# SCH.net
KiCad netlist of a schematic drawn in EasyEDA Pro
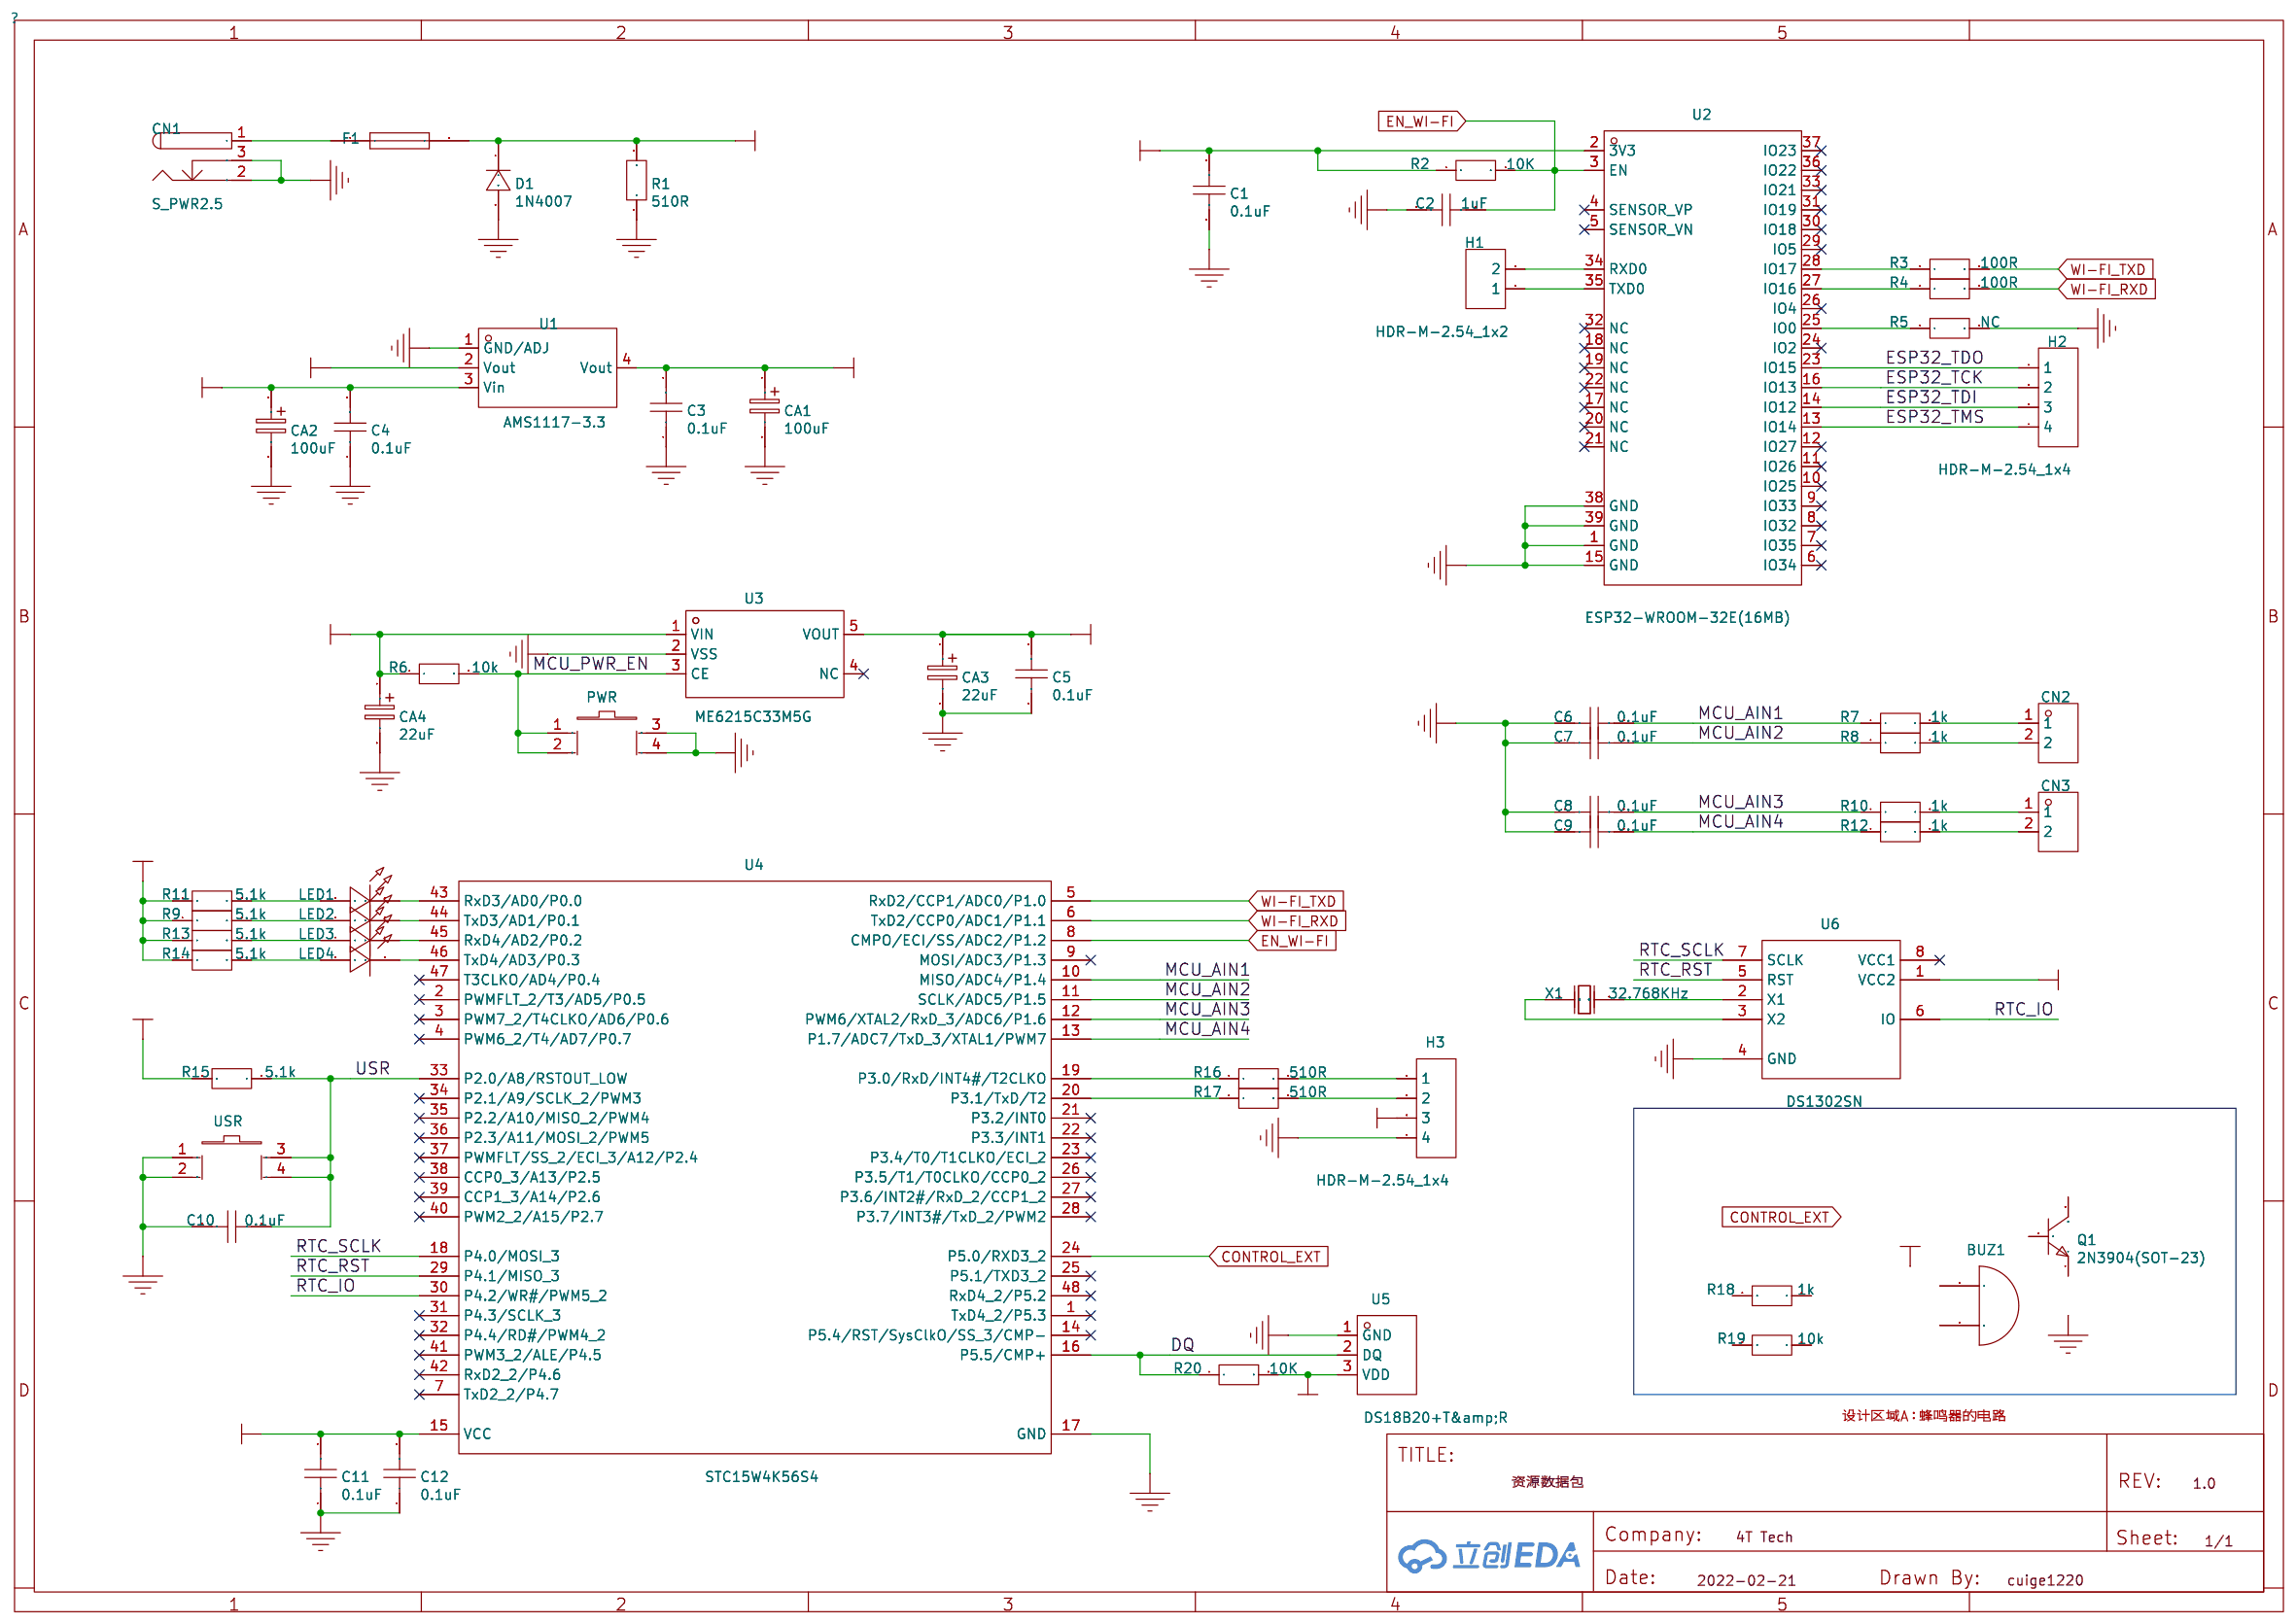
[diagram p0: schematic sheet]

(export (version "E")
  (design (tool "Eeschema 10.0.6"))
  (components
    (comp (ref "BUZ1") (value "BUZ1") (libsource (lib "easyedapro") (part "BUZ1")))
    (comp (ref "C1") (value "0.1uF") (libsource (lib "easyedapro") (part "0.1uF")))
    (comp (ref "C2") (value "1uF") (libsource (lib "easyedapro") (part "1uF")))
    (comp (ref "C3") (value "0.1uF") (libsource (lib "easyedapro") (part "0.1uF")))
    (comp (ref "C4") (value "0.1uF") (libsource (lib "easyedapro") (part "0.1uF")))
    (comp (ref "C5") (value "0.1uF") (libsource (lib "easyedapro") (part "0.1uF")))
    (comp (ref "C6") (value "0.1uF") (libsource (lib "easyedapro") (part "0.1uF")))
    (comp (ref "C7") (value "0.1uF") (libsource (lib "easyedapro") (part "0.1uF")))
    (comp (ref "C8") (value "0.1uF") (libsource (lib "easyedapro") (part "0.1uF")))
    (comp (ref "C9") (value "0.1uF") (libsource (lib "easyedapro") (part "0.1uF")))
    (comp (ref "C10") (value "0.1uF") (libsource (lib "easyedapro") (part "0.1uF")))
    (comp (ref "C11") (value "0.1uF") (libsource (lib "easyedapro") (part "0.1uF")))
    (comp (ref "C12") (value "0.1uF") (libsource (lib "easyedapro") (part "0.1uF")))
    (comp (ref "CA1") (value "100uF") (libsource (lib "easyedapro") (part "100uF")))
    (comp (ref "CA2") (value "100uF") (libsource (lib "easyedapro") (part "100uF")))
    (comp (ref "CA3") (value "22uF") (libsource (lib "easyedapro") (part "22uF")))
    (comp (ref "CA4") (value "22uF") (libsource (lib "easyedapro") (part "22uF")))
    (comp (ref "CN1") (value "S_PWR2.5") (libsource (lib "easyedapro") (part "S_PWR2.5")))
    (comp (ref "CN2")
      (value "DB128L-5.08-2P")
      (fields (field (name "Manufacturer") "DIBO"))
      (libsource (lib "easyedapro") (part "DB128L-5.08-2P"))
    )
    (comp (ref "CN3")
      (value "DB128L-5.08-2P")
      (fields (field (name "Manufacturer") "DIBO"))
      (libsource (lib "easyedapro") (part "DB128L-5.08-2P"))
    )
    (comp (ref "D1")
      (value "1N4007")
      (fields (field (name "Manufacturer") "SEMTECH"))
      (libsource (lib "easyedapro") (part "1N4007"))
    )
    (comp (ref "F1")
      (value "ASMD1210-075")
      (fields (field (name "Publisher") "Altium Limited"))
      (libsource (lib "easyedapro") (part "ASMD1210-075"))
    )
    (comp (ref "H1") (value "HDR-M-2.54_1x2") (libsource (lib "easyedapro") (part "HDR-M-2.54_1x2")))
    (comp (ref "H2") (value "HDR-M-2.54_1x4") (libsource (lib "easyedapro") (part "HDR-M-2.54_1x4")))
    (comp (ref "H3") (value "HDR-M-2.54_1x4") (libsource (lib "easyedapro") (part "HDR-M-2.54_1x4")))
    (comp (ref "LED1")
      (value "LED-TH-3mm_R")
      (fields
        (field (name "Manufacturer Part") "204-10SDRD/S530-A3-L")
        (field (name "Manufacturer") "EVERLIGHT(台湾亿光)")
      )
      (libsource (lib "easyedapro") (part "LED-TH-3mm_R"))
    )
    (comp (ref "LED2")
      (value "LED-TH-3mm_R")
      (fields
        (field (name "Manufacturer Part") "204-10SDRD/S530-A3-L")
        (field (name "Manufacturer") "EVERLIGHT(台湾亿光)")
      )
      (libsource (lib "easyedapro") (part "LED-TH-3mm_R"))
    )
    (comp (ref "LED3")
      (value "LED-TH-3mm_R")
      (fields
        (field (name "Manufacturer Part") "204-10SDRD/S530-A3-L")
        (field (name "Manufacturer") "EVERLIGHT(台湾亿光)")
      )
      (libsource (lib "easyedapro") (part "LED-TH-3mm_R"))
    )
    (comp (ref "LED4")
      (value "LED-TH-3mm_R")
      (fields
        (field (name "Manufacturer Part") "204-10SDRD/S530-A3-L")
        (field (name "Manufacturer") "EVERLIGHT(台湾亿光)")
      )
      (libsource (lib "easyedapro") (part "LED-TH-3mm_R"))
    )
    (comp (ref "PWR")
      (value "6x6x6Plastic head")
      (fields (field (name "Manufacturer") "ReliaPro"))
      (libsource (lib "easyedapro") (part "6x6x6Plastic head"))
    )
    (comp (ref "Q1")
      (value "2N3904(SOT-23)")
      (fields (field (name "Manufacturer Part") "2n3904S-RTK/PS") (field (name "Manufacturer") "KEC"))
      (libsource (lib "easyedapro") (part "2N3904(SOT-23)"))
    )
    (comp (ref "R1") (value "510R") (libsource (lib "easyedapro") (part "510R")))
    (comp (ref "R2") (value "10K") (libsource (lib "easyedapro") (part "10k")))
    (comp (ref "R3") (value "100R") (libsource (lib "easyedapro") (part "100R")))
    (comp (ref "R4") (value "100R") (libsource (lib "easyedapro") (part "100R")))
    (comp (ref "R5") (value "NC") (libsource (lib "easyedapro") (part "NC")))
    (comp (ref "R6") (value "10k") (libsource (lib "easyedapro") (part "10k")))
    (comp (ref "R7") (value "1k") (libsource (lib "easyedapro") (part "1K")))
    (comp (ref "R8") (value "1k") (libsource (lib "easyedapro") (part "1K")))
    (comp (ref "R9") (value "5.1k") (libsource (lib "easyedapro") (part "5.1k")))
    (comp (ref "R10") (value "1k") (libsource (lib "easyedapro") (part "1K")))
    (comp (ref "R11") (value "5.1k") (libsource (lib "easyedapro") (part "5.1k")))
    (comp (ref "R12") (value "1k") (libsource (lib "easyedapro") (part "1K")))
    (comp (ref "R13") (value "5.1k") (libsource (lib "easyedapro") (part "5.1k")))
    (comp (ref "R14") (value "5.1k") (libsource (lib "easyedapro") (part "5.1k")))
    (comp (ref "R15") (value "5.1k") (libsource (lib "easyedapro") (part "5.1k")))
    (comp (ref "R16") (value "510R") (libsource (lib "easyedapro") (part "510R")))
    (comp (ref "R17") (value "510R") (libsource (lib "easyedapro") (part "510R")))
    (comp (ref "R18") (value "1k") (libsource (lib "easyedapro") (part "1K")))
    (comp (ref "R19") (value "10k") (libsource (lib "easyedapro") (part "10k")))
    (comp (ref "R20") (value "10K") (libsource (lib "easyedapro") (part "10k")))
    (comp (ref "U1")
      (value "AMS1117-3.3")
      (fields (field (name "Manufacturer") "AMS"))
      (libsource (lib "easyedapro") (part "AMS1117-3.3"))
    )
    (comp (ref "U2")
      (value "ESP32-WROOM-32E(16MB)")
      (fields (field (name "Manufacturer") "Espressif Systems"))
      (libsource (lib "easyedapro") (part "ESP32-WROOM-32E(16MB)"))
    )
    (comp (ref "U3")
      (value "ME6215C33M5G")
      (fields (field (name "Manufacturer") "MICRONE"))
      (libsource (lib "easyedapro") (part "ME6215C33M5G"))
    )
    (comp (ref "U4")
      (value "STC15W4K56S4")
      (fields (field (name "Manufacturer") "STC"))
      (libsource (lib "easyedapro") (part "STC15W4K56S4"))
    )
    (comp (ref "U5")
      (value "DS18B20+T&amp;R")
      (fields (field (name "Manufacturer Part") "DS18B20+T&R") (field (name "Manufacturer") "MAXIM(美信)"))
      (libsource (lib "easyedapro") (part "DS18B20+T&amp;R"))
    )
    (comp (ref "U6") (value "DS1302SN") (libsource (lib "easyedapro") (part "DS1302SN")))
    (comp (ref "USR")
      (value "6x6x6Plastic head")
      (fields (field (name "Manufacturer") "ReliaPro"))
      (libsource (lib "easyedapro") (part "6x6x6Plastic head"))
    )
    (comp (ref "X1")
      (value "32.768KHz")
      (fields (field (name "Manufacturer Part") "CFS-20632768EZFB") (field (name "Manufacturer") "CITIZEN"))
      (libsource (lib "easyedapro") (part "32.768KHz"))
    )
  )
  (nets
    (net (code "1") (name "+5V0") (class "Default")
      (node (ref "C4") (pin "2") (pinfunction "2_2") (pintype "input"))
      (node (ref "CA2") (pin "1") (pinfunction "1_1") (pintype "input"))
      (node (ref "CA4") (pin "1") (pinfunction "1_1") (pintype "input"))
      (node (ref "D1") (pin "1") (pinfunction "1_1") (pintype "input"))
      (node (ref "F1") (pin "2") (pinfunction "2_2") (pintype "input"))
      (node (ref "R1") (pin "2") (pinfunction "2_2") (pintype "input"))
      (node (ref "R6") (pin "1") (pinfunction "1_1") (pintype "input"))
      (node (ref "U1") (pin "3") (pinfunction "Vin_3") (pintype "input"))
      (node (ref "U3") (pin "1") (pinfunction "VIN_1") (pintype "input"))
    )
    (net (code "2") (name "/DQ") (class "Default")
      (node (ref "R20") (pin "1") (pinfunction "1_1") (pintype "input"))
      (node (ref "U4") (pin "16") (pinfunction "P5.5/CMP+_16") (pintype "input"))
      (node (ref "U5") (pin "2") (pinfunction "DQ_2") (pintype "input"))
    )
    (net (code "3") (name "/ESP32_TCK") (class "Default")
      (node (ref "H2") (pin "2") (pinfunction "2_2") (pintype "input"))
      (node (ref "U2") (pin "16") (pinfunction "IO13_16") (pintype "input"))
    )
    (net (code "4") (name "/ESP32_TDI") (class "Default")
      (node (ref "H2") (pin "3") (pinfunction "3_3") (pintype "input"))
      (node (ref "U2") (pin "14") (pinfunction "IO12_14") (pintype "input"))
    )
    (net (code "5") (name "/ESP32_TDO") (class "Default")
      (node (ref "H2") (pin "1") (pinfunction "1_1") (pintype "input"))
      (node (ref "U2") (pin "23") (pinfunction "IO15_23") (pintype "input"))
    )
    (net (code "6") (name "/ESP32_TMS") (class "Default")
      (node (ref "H2") (pin "4") (pinfunction "4_4") (pintype "input"))
      (node (ref "U2") (pin "13") (pinfunction "IO14_13") (pintype "input"))
    )
    (net (code "7") (name "/MCU_AIN1") (class "Default")
      (node (ref "C6") (pin "2") (pinfunction "2_2") (pintype "input"))
      (node (ref "R7") (pin "1") (pinfunction "1_1") (pintype "input"))
      (node (ref "U4") (pin "10") (pinfunction "MISO/ADC4/P1.4_10") (pintype "input"))
    )
    (net (code "8") (name "/MCU_AIN2") (class "Default")
      (node (ref "C7") (pin "2") (pinfunction "2_2") (pintype "input"))
      (node (ref "R8") (pin "1") (pinfunction "1_1") (pintype "input"))
      (node (ref "U4") (pin "11") (pinfunction "SCLK/ADC5/P1.5_11") (pintype "input"))
    )
    (net (code "9") (name "/MCU_AIN3") (class "Default")
      (node (ref "C8") (pin "2") (pinfunction "2_2") (pintype "input"))
      (node (ref "R10") (pin "1") (pinfunction "1_1") (pintype "input"))
      (node (ref "U4") (pin "12") (pinfunction "PWM6/XTAL2/RxD_3/ADC6/P1.6_12") (pintype "input"))
    )
    (net (code "10") (name "/MCU_AIN4") (class "Default")
      (node (ref "C9") (pin "2") (pinfunction "2_2") (pintype "input"))
      (node (ref "R12") (pin "1") (pinfunction "1_1") (pintype "input"))
      (node (ref "U4") (pin "13") (pinfunction "P1.7/ADC7/TxD_3/XTAL1/PWM7_13") (pintype "input"))
    )
    (net (code "11") (name "/MCU_PWR_EN") (class "Default")
      (node (ref "PWR") (pin "1") (pinfunction "1_1") (pintype "input"))
      (node (ref "PWR") (pin "2") (pinfunction "2_2") (pintype "input"))
      (node (ref "R6") (pin "2") (pinfunction "2_2") (pintype "input"))
      (node (ref "U3") (pin "3") (pinfunction "CE_3") (pintype "input"))
    )
    (net (code "12") (name "/RTC_IO") (class "Default")
      (node (ref "U4") (pin "30") (pinfunction "P4.2/WR#/PWM5_2_30") (pintype "input"))
      (node (ref "U6") (pin "6") (pinfunction "IO_6") (pintype "bidirectional"))
    )
    (net (code "13") (name "/RTC_RST") (class "Default")
      (node (ref "U4") (pin "29") (pinfunction "P4.1/MISO_3_29") (pintype "input"))
      (node (ref "U6") (pin "5") (pinfunction "RST_5") (pintype "input"))
    )
    (net (code "14") (name "/RTC_SCLK") (class "Default")
      (node (ref "U4") (pin "18") (pinfunction "P4.0/MOSI_3_18") (pintype "input"))
      (node (ref "U6") (pin "7") (pinfunction "SCLK_7") (pintype "input"))
    )
    (net (code "15") (name "/USR") (class "Default")
      (node (ref "C10") (pin "1") (pinfunction "1_1") (pintype "input"))
      (node (ref "R15") (pin "1") (pinfunction "1_1") (pintype "input"))
      (node (ref "U4") (pin "33") (pinfunction "P2.0/A8/RSTOUT_LOW_33") (pintype "input"))
      (node (ref "USR") (pin "3") (pinfunction "3_3") (pintype "input"))
      (node (ref "USR") (pin "4") (pinfunction "4_4") (pintype "input"))
    )
    (net (code "16") (name "3.3V_MCU") (class "Default")
      (node (ref "C11") (pin "2") (pinfunction "2_2") (pintype "input"))
      (node (ref "C12") (pin "2") (pinfunction "2_2") (pintype "input"))
      (node (ref "C5") (pin "2") (pinfunction "2_2") (pintype "input"))
      (node (ref "CA3") (pin "1") (pinfunction "1_1") (pintype "input"))
      (node (ref "H3") (pin "3") (pinfunction "3_3") (pintype "input"))
      (node (ref "R11") (pin "1") (pinfunction "1_1") (pintype "input"))
      (node (ref "R13") (pin "1") (pinfunction "1_1") (pintype "input"))
      (node (ref "R14") (pin "1") (pinfunction "1_1") (pintype "input"))
      (node (ref "R15") (pin "2") (pinfunction "2_2") (pintype "input"))
      (node (ref "R20") (pin "2") (pinfunction "2_2") (pintype "input"))
      (node (ref "R9") (pin "1") (pinfunction "1_1") (pintype "input"))
      (node (ref "U3") (pin "5") (pinfunction "VOUT_5") (pintype "input"))
      (node (ref "U4") (pin "15") (pinfunction "VCC_15") (pintype "input"))
      (node (ref "U5") (pin "3") (pinfunction "VDD_3") (pintype "input"))
      (node (ref "U6") (pin "1") (pinfunction "VCC2_1") (pintype "input"))
    )
    (net (code "17") (name "3.3V_WIFI") (class "Default")
      (node (ref "C1") (pin "2") (pinfunction "2_2") (pintype "input"))
      (node (ref "C3") (pin "2") (pinfunction "2_2") (pintype "input"))
      (node (ref "CA1") (pin "1") (pinfunction "1_1") (pintype "input"))
      (node (ref "R2") (pin "1") (pinfunction "1_1") (pintype "input"))
      (node (ref "U1") (pin "2") (pinfunction "Vout_2") (pintype "input"))
      (node (ref "U1") (pin "4") (pinfunction "Vout_4") (pintype "input"))
      (node (ref "U2") (pin "2") (pinfunction "3V3_2") (pintype "input"))
    )
    (net (code "18") (name "CONTROL_EXT") (class "Default")
      (node (ref "U4") (pin "24") (pinfunction "P5.0/RXD3_2_24") (pintype "input"))
    )
    (net (code "19") (name "EN_WI-FI") (class "Default")
      (node (ref "C2") (pin "1") (pinfunction "1_1") (pintype "input"))
      (node (ref "R2") (pin "2") (pinfunction "2_2") (pintype "input"))
      (node (ref "U2") (pin "3") (pinfunction "EN_3") (pintype "input"))
      (node (ref "U4") (pin "8") (pinfunction "CMPO/ECI/SS/ADC2/P1.2_8") (pintype "input"))
    )
    (net (code "20") (name "GND") (class "Default")
      (node (ref "C1") (pin "1") (pinfunction "1_1") (pintype "input"))
      (node (ref "C10") (pin "2") (pinfunction "2_2") (pintype "input"))
      (node (ref "C11") (pin "1") (pinfunction "1_1") (pintype "input"))
      (node (ref "C12") (pin "1") (pinfunction "1_1") (pintype "input"))
      (node (ref "C2") (pin "2") (pinfunction "2_2") (pintype "input"))
      (node (ref "C3") (pin "1") (pinfunction "1_1") (pintype "input"))
      (node (ref "C4") (pin "1") (pinfunction "1_1") (pintype "input"))
      (node (ref "C5") (pin "1") (pinfunction "1_1") (pintype "input"))
      (node (ref "C6") (pin "1") (pinfunction "1_1") (pintype "input"))
      (node (ref "C7") (pin "1") (pinfunction "1_1") (pintype "input"))
      (node (ref "C8") (pin "1") (pinfunction "1_1") (pintype "input"))
      (node (ref "C9") (pin "1") (pinfunction "1_1") (pintype "input"))
      (node (ref "CA1") (pin "2") (pinfunction "2_2") (pintype "input"))
      (node (ref "CA2") (pin "2") (pinfunction "2_2") (pintype "input"))
      (node (ref "CA3") (pin "2") (pinfunction "2_2") (pintype "input"))
      (node (ref "CA4") (pin "2") (pinfunction "2_2") (pintype "input"))
      (node (ref "CN1") (pin "2") (pinfunction "2_2") (pintype "input"))
      (node (ref "CN1") (pin "3") (pinfunction "3_3") (pintype "input"))
      (node (ref "D1") (pin "2") (pinfunction "2_2") (pintype "input"))
      (node (ref "H3") (pin "4") (pinfunction "4_4") (pintype "input"))
      (node (ref "PWR") (pin "3") (pinfunction "3_3") (pintype "input"))
      (node (ref "PWR") (pin "4") (pinfunction "4_4") (pintype "input"))
      (node (ref "R1") (pin "1") (pinfunction "1_1") (pintype "input"))
      (node (ref "R5") (pin "2") (pinfunction "2_2") (pintype "input"))
      (node (ref "U1") (pin "1") (pinfunction "GND/ADJ_1") (pintype "input"))
      (node (ref "U2") (pin "1") (pinfunction "GND_1") (pintype "input"))
      (node (ref "U2") (pin "15") (pinfunction "GND_15") (pintype "input"))
      (node (ref "U2") (pin "38") (pinfunction "GND_38") (pintype "input"))
      (node (ref "U2") (pin "39") (pinfunction "GND_39") (pintype "input"))
      (node (ref "U3") (pin "2") (pinfunction "VSS_2") (pintype "input"))
      (node (ref "U4") (pin "17") (pinfunction "GND_17") (pintype "input"))
      (node (ref "U5") (pin "1") (pinfunction "GND_1") (pintype "input"))
      (node (ref "U6") (pin "4") (pinfunction "GND_4") (pintype "input"))
      (node (ref "USR") (pin "1") (pinfunction "1_1") (pintype "input"))
      (node (ref "USR") (pin "2") (pinfunction "2_2") (pintype "input"))
    )
    (net (code "21") (name "Net-(CN1-Pad1)") (class "Default")
      (node (ref "CN1") (pin "1") (pinfunction "1_1") (pintype "input"))
      (node (ref "F1") (pin "1") (pinfunction "1_1") (pintype "input"))
    )
    (net (code "22") (name "Net-(CN2-Pad1)") (class "Default")
      (node (ref "CN2") (pin "1") (pinfunction "1_1") (pintype "input"))
      (node (ref "R7") (pin "2") (pinfunction "2_2") (pintype "input"))
    )
    (net (code "23") (name "Net-(CN2-Pad2)") (class "Default")
      (node (ref "CN2") (pin "2") (pinfunction "2_2") (pintype "input"))
      (node (ref "R8") (pin "2") (pinfunction "2_2") (pintype "input"))
    )
    (net (code "24") (name "Net-(CN3-Pad1)") (class "Default")
      (node (ref "CN3") (pin "1") (pinfunction "1_1") (pintype "input"))
      (node (ref "R10") (pin "2") (pinfunction "2_2") (pintype "input"))
    )
    (net (code "25") (name "Net-(CN3-Pad2)") (class "Default")
      (node (ref "CN3") (pin "2") (pinfunction "2_2") (pintype "input"))
      (node (ref "R12") (pin "2") (pinfunction "2_2") (pintype "input"))
    )
    (net (code "26") (name "Net-(H3-Pad1)") (class "Default")
      (node (ref "H3") (pin "1") (pinfunction "1_1") (pintype "input"))
      (node (ref "R16") (pin "2") (pinfunction "2_2") (pintype "input"))
    )
    (net (code "27") (name "Net-(H3-Pad2)") (class "Default")
      (node (ref "H3") (pin "2") (pinfunction "2_2") (pintype "input"))
      (node (ref "R17") (pin "2") (pinfunction "2_2") (pintype "input"))
    )
    (net (code "28") (name "Net-(LED1-Pad1)") (class "Default")
      (node (ref "LED1") (pin "1") (pinfunction "1_1") (pintype "input"))
      (node (ref "R9") (pin "2") (pinfunction "2_2") (pintype "input"))
    )
    (net (code "29") (name "Net-(LED2-Pad1)") (class "Default")
      (node (ref "LED2") (pin "1") (pinfunction "1_1") (pintype "input"))
      (node (ref "R11") (pin "2") (pinfunction "2_2") (pintype "input"))
    )
    (net (code "30") (name "Net-(LED3-Pad1)") (class "Default")
      (node (ref "LED3") (pin "1") (pinfunction "1_1") (pintype "input"))
      (node (ref "R13") (pin "2") (pinfunction "2_2") (pintype "input"))
    )
    (net (code "31") (name "Net-(LED4-Pad1)") (class "Default")
      (node (ref "LED4") (pin "1") (pinfunction "1_1") (pintype "input"))
      (node (ref "R14") (pin "2") (pinfunction "2_2") (pintype "input"))
    )
    (net (code "32") (name "Net-(U2-IO0)") (class "Default")
      (node (ref "R5") (pin "1") (pinfunction "1_1") (pintype "input"))
      (node (ref "U2") (pin "25") (pinfunction "IO0_25") (pintype "input"))
    )
    (net (code "33") (name "Net-(U2-IO16)") (class "Default")
      (node (ref "R4") (pin "1") (pinfunction "1_1") (pintype "input"))
      (node (ref "U2") (pin "27") (pinfunction "IO16_27") (pintype "input"))
    )
    (net (code "34") (name "Net-(U2-IO17)") (class "Default")
      (node (ref "R3") (pin "1") (pinfunction "1_1") (pintype "input"))
      (node (ref "U2") (pin "28") (pinfunction "IO17_28") (pintype "input"))
    )
    (net (code "35") (name "Net-(U2-RXD0)") (class "Default")
      (node (ref "H1") (pin "2") (pinfunction "2_2") (pintype "input"))
      (node (ref "U2") (pin "34") (pinfunction "RXD0_34") (pintype "input"))
    )
    (net (code "36") (name "Net-(U2-TXD0)") (class "Default")
      (node (ref "H1") (pin "1") (pinfunction "1_1") (pintype "input"))
      (node (ref "U2") (pin "35") (pinfunction "TXD0_35") (pintype "input"))
    )
    (net (code "37") (name "Net-(U4-P3.0{slash}RxD{slash}INT4#{slash}T2CLKO)") (class "Default")
      (node (ref "R16") (pin "1") (pinfunction "1_1") (pintype "input"))
      (node (ref "U4") (pin "19") (pinfunction "P3.0/RxD/INT4#/T2CLKO_19") (pintype "input"))
    )
    (net (code "38") (name "Net-(U4-P3.1{slash}TxD{slash}T2)") (class "Default")
      (node (ref "R17") (pin "1") (pinfunction "1_1") (pintype "input"))
      (node (ref "U4") (pin "20") (pinfunction "P3.1/TxD/T2_20") (pintype "input"))
    )
    (net (code "39") (name "Net-(U4-RxD3{slash}AD0{slash}P0.0)") (class "Default")
      (node (ref "LED1") (pin "2") (pinfunction "2_2") (pintype "input"))
      (node (ref "U4") (pin "43") (pinfunction "RxD3/AD0/P0.0_43") (pintype "input"))
    )
    (net (code "40") (name "Net-(U4-RxD4{slash}AD2{slash}P0.2)") (class "Default")
      (node (ref "LED3") (pin "2") (pinfunction "2_2") (pintype "input"))
      (node (ref "U4") (pin "45") (pinfunction "RxD4/AD2/P0.2_45") (pintype "input"))
    )
    (net (code "41") (name "Net-(U4-TxD3{slash}AD1{slash}P0.1)") (class "Default")
      (node (ref "LED2") (pin "2") (pinfunction "2_2") (pintype "input"))
      (node (ref "U4") (pin "44") (pinfunction "TxD3/AD1/P0.1_44") (pintype "input"))
    )
    (net (code "42") (name "Net-(U4-TxD4{slash}AD3{slash}P0.3)") (class "Default")
      (node (ref "LED4") (pin "2") (pinfunction "2_2") (pintype "input"))
      (node (ref "U4") (pin "46") (pinfunction "TxD4/AD3/P0.3_46") (pintype "input"))
    )
    (net (code "43") (name "Net-(U6-X1)") (class "Default")
      (node (ref "U6") (pin "2") (pinfunction "X1_2") (pintype "input"))
      (node (ref "X1") (pin "2") (pinfunction "OSC2_2") (pintype "input"))
    )
    (net (code "44") (name "Net-(U6-X2)") (class "Default")
      (node (ref "U6") (pin "3") (pinfunction "X2_3") (pintype "input"))
      (node (ref "X1") (pin "1") (pinfunction "OSC1_1") (pintype "input"))
    )
    (net (code "45") (name "WI-FI_RXD") (class "Default")
      (node (ref "R4") (pin "2") (pinfunction "2_2") (pintype "input"))
      (node (ref "U4") (pin "6") (pinfunction "TxD2/CCP0/ADC1/P1.1_6") (pintype "input"))
    )
    (net (code "46") (name "WI-FI_TXD") (class "Default")
      (node (ref "R3") (pin "2") (pinfunction "2_2") (pintype "input"))
      (node (ref "U4") (pin "5") (pinfunction "RxD2/CCP1/ADC0/P1.0_5") (pintype "input"))
    )
    (net (code "47") (name "unconnected-(BUZ1-A-Pad1)") (class "Default")
      (node (ref "BUZ1") (pin "1") (pinfunction "A_1") (pintype "input"))
    )
    (net (code "48") (name "unconnected-(BUZ1-B-Pad2)") (class "Default")
      (node (ref "BUZ1") (pin "2") (pinfunction "B_2") (pintype "input"))
    )
    (net (code "49") (name "unconnected-(Q1-B-Pad2)") (class "Default")
      (node (ref "Q1") (pin "2") (pinfunction "B_2") (pintype "input"))
    )
    (net (code "50") (name "unconnected-(Q1-C-Pad3)") (class "Default")
      (node (ref "Q1") (pin "3") (pinfunction "C_3") (pintype "input"))
    )
    (net (code "51") (name "unconnected-(Q1-E-Pad1)") (class "Default")
      (node (ref "Q1") (pin "1") (pinfunction "E_1") (pintype "input"))
    )
    (net (code "52") (name "unconnected-(R18-Pad1)") (class "Default")
      (node (ref "R18") (pin "1") (pinfunction "1_1") (pintype "input"))
    )
    (net (code "53") (name "unconnected-(R18-Pad2)") (class "Default")
      (node (ref "R18") (pin "2") (pinfunction "2_2") (pintype "input"))
    )
    (net (code "54") (name "unconnected-(R19-Pad1)") (class "Default")
      (node (ref "R19") (pin "1") (pinfunction "1_1") (pintype "input"))
    )
    (net (code "55") (name "unconnected-(R19-Pad2)") (class "Default")
      (node (ref "R19") (pin "2") (pinfunction "2_2") (pintype "input"))
    )
    (net (code "56") (name "unconnected-(U2-IO2-Pad24)") (class "Default")
      (node (ref "U2") (pin "24") (pinfunction "IO2_24") (pintype "input+no_connect"))
    )
    (net (code "57") (name "unconnected-(U2-IO4-Pad26)") (class "Default")
      (node (ref "U2") (pin "26") (pinfunction "IO4_26") (pintype "input+no_connect"))
    )
    (net (code "58") (name "unconnected-(U2-IO5-Pad29)") (class "Default")
      (node (ref "U2") (pin "29") (pinfunction "IO5_29") (pintype "input+no_connect"))
    )
    (net (code "59") (name "unconnected-(U2-IO18-Pad30)") (class "Default")
      (node (ref "U2") (pin "30") (pinfunction "IO18_30") (pintype "input+no_connect"))
    )
    (net (code "60") (name "unconnected-(U2-IO19-Pad31)") (class "Default")
      (node (ref "U2") (pin "31") (pinfunction "IO19_31") (pintype "input+no_connect"))
    )
    (net (code "61") (name "unconnected-(U2-IO21-Pad33)") (class "Default")
      (node (ref "U2") (pin "33") (pinfunction "IO21_33") (pintype "input+no_connect"))
    )
    (net (code "62") (name "unconnected-(U2-IO22-Pad36)") (class "Default")
      (node (ref "U2") (pin "36") (pinfunction "IO22_36") (pintype "input+no_connect"))
    )
    (net (code "63") (name "unconnected-(U2-IO23-Pad37)") (class "Default")
      (node (ref "U2") (pin "37") (pinfunction "IO23_37") (pintype "input+no_connect"))
    )
    (net (code "64") (name "unconnected-(U2-IO25-Pad10)") (class "Default")
      (node (ref "U2") (pin "10") (pinfunction "IO25_10") (pintype "input+no_connect"))
    )
    (net (code "65") (name "unconnected-(U2-IO26-Pad11)") (class "Default")
      (node (ref "U2") (pin "11") (pinfunction "IO26_11") (pintype "input+no_connect"))
    )
    (net (code "66") (name "unconnected-(U2-IO27-Pad12)") (class "Default")
      (node (ref "U2") (pin "12") (pinfunction "IO27_12") (pintype "input+no_connect"))
    )
    (net (code "67") (name "unconnected-(U2-IO32-Pad8)") (class "Default")
      (node (ref "U2") (pin "8") (pinfunction "IO32_8") (pintype "input+no_connect"))
    )
    (net (code "68") (name "unconnected-(U2-IO33-Pad9)") (class "Default")
      (node (ref "U2") (pin "9") (pinfunction "IO33_9") (pintype "input+no_connect"))
    )
    (net (code "69") (name "unconnected-(U2-IO34-Pad6)") (class "Default")
      (node (ref "U2") (pin "6") (pinfunction "IO34_6") (pintype "input+no_connect"))
    )
    (net (code "70") (name "unconnected-(U2-IO35-Pad7)") (class "Default")
      (node (ref "U2") (pin "7") (pinfunction "IO35_7") (pintype "input+no_connect"))
    )
    (net (code "71") (name "unconnected-(U2-NC-Pad17)") (class "Default")
      (node (ref "U2") (pin "17") (pinfunction "NC_17") (pintype "input+no_connect"))
    )
    (net (code "72") (name "unconnected-(U2-NC-Pad18)") (class "Default")
      (node (ref "U2") (pin "18") (pinfunction "NC_18") (pintype "input+no_connect"))
    )
    (net (code "73") (name "unconnected-(U2-NC-Pad19)") (class "Default")
      (node (ref "U2") (pin "19") (pinfunction "NC_19") (pintype "input+no_connect"))
    )
    (net (code "74") (name "unconnected-(U2-NC-Pad20)") (class "Default")
      (node (ref "U2") (pin "20") (pinfunction "NC_20") (pintype "input+no_connect"))
    )
    (net (code "75") (name "unconnected-(U2-NC-Pad21)") (class "Default")
      (node (ref "U2") (pin "21") (pinfunction "NC_21") (pintype "input+no_connect"))
    )
    (net (code "76") (name "unconnected-(U2-NC-Pad22)") (class "Default")
      (node (ref "U2") (pin "22") (pinfunction "NC_22") (pintype "input+no_connect"))
    )
    (net (code "77") (name "unconnected-(U2-NC-Pad32)") (class "Default")
      (node (ref "U2") (pin "32") (pinfunction "NC_32") (pintype "input+no_connect"))
    )
    (net (code "78") (name "unconnected-(U2-SENSOR_VN-Pad5)") (class "Default")
      (node (ref "U2") (pin "5") (pinfunction "SENSOR_VN_5") (pintype "input+no_connect"))
    )
    (net (code "79") (name "unconnected-(U2-SENSOR_VP-Pad4)") (class "Default")
      (node (ref "U2") (pin "4") (pinfunction "SENSOR_VP_4") (pintype "input+no_connect"))
    )
    (net (code "80") (name "unconnected-(U3-NC-Pad4)") (class "Default")
      (node (ref "U3") (pin "4") (pinfunction "NC_4") (pintype "input+no_connect"))
    )
    (net (code "81") (name "unconnected-(U4-CCP0_3{slash}A13{slash}P2.5-Pad38)") (class "Default")
      (node (ref "U4") (pin "38") (pinfunction "CCP0_3/A13/P2.5_38") (pintype "input+no_connect"))
    )
    (net (code "82") (name "unconnected-(U4-CCP1_3{slash}A14{slash}P2.6-Pad39)") (class "Default")
      (node (ref "U4") (pin "39") (pinfunction "CCP1_3/A14/P2.6_39") (pintype "input+no_connect"))
    )
    (net (code "83") (name "unconnected-(U4-MOSI{slash}ADC3{slash}P1.3-Pad9)") (class "Default")
      (node (ref "U4") (pin "9") (pinfunction "MOSI/ADC3/P1.3_9") (pintype "input+no_connect"))
    )
    (net (code "84") (name "unconnected-(U4-P2.1{slash}A9{slash}SCLK_2{slash}PWM3-Pad34)") (class "Default")
      (node (ref "U4") (pin "34") (pinfunction "P2.1/A9/SCLK_2/PWM3_34") (pintype "input+no_connect"))
    )
    (net (code "85") (name "unconnected-(U4-P2.2{slash}A10{slash}MISO_2{slash}PWM4-Pad35)") (class "Default")
      (node (ref "U4") (pin "35") (pinfunction "P2.2/A10/MISO_2/PWM4_35") (pintype "input+no_connect"))
    )
    (net (code "86") (name "unconnected-(U4-P2.3{slash}A11{slash}MOSI_2{slash}PWM5-Pad36)") (class "Default")
      (node (ref "U4") (pin "36") (pinfunction "P2.3/A11/MOSI_2/PWM5_36") (pintype "input+no_connect"))
    )
    (net (code "87") (name "unconnected-(U4-P3.2{slash}INT0-Pad21)") (class "Default")
      (node (ref "U4") (pin "21") (pinfunction "P3.2/INT0_21") (pintype "input+no_connect"))
    )
    (net (code "88") (name "unconnected-(U4-P3.3{slash}INT1-Pad22)") (class "Default")
      (node (ref "U4") (pin "22") (pinfunction "P3.3/INT1_22") (pintype "input+no_connect"))
    )
    (net (code "89") (name "unconnected-(U4-P3.4{slash}T0{slash}T1CLKO{slash}ECI_2-Pad23)") (class "Default")
      (node (ref "U4") (pin "23") (pinfunction "P3.4/T0/T1CLKO/ECI_2_23") (pintype "input+no_connect"))
    )
    (net (code "90") (name "unconnected-(U4-P3.5{slash}T1{slash}T0CLKO{slash}CCP0_2-Pad26)") (class "Default")
      (node (ref "U4") (pin "26") (pinfunction "P3.5/T1/T0CLKO/CCP0_2_26") (pintype "input+no_connect"))
    )
    (net (code "91") (name "unconnected-(U4-P3.6{slash}INT2#{slash}RxD_2{slash}CCP1_2-Pad27)") (class "Default")
      (node (ref "U4") (pin "27") (pinfunction "P3.6/INT2#/RxD_2/CCP1_2_27") (pintype "input+no_connect"))
    )
    (net (code "92") (name "unconnected-(U4-P3.7{slash}INT3#{slash}TxD_2{slash}PWM2-Pad28)") (class "Default")
      (node (ref "U4") (pin "28") (pinfunction "P3.7/INT3#/TxD_2/PWM2_28") (pintype "input+no_connect"))
    )
    (net (code "93") (name "unconnected-(U4-P4.3{slash}SCLK_3-Pad31)") (class "Default")
      (node (ref "U4") (pin "31") (pinfunction "P4.3/SCLK_3_31") (pintype "input+no_connect"))
    )
    (net (code "94") (name "unconnected-(U4-P4.4{slash}RD#{slash}PWM4_2-Pad32)") (class "Default")
      (node (ref "U4") (pin "32") (pinfunction "P4.4/RD#/PWM4_2_32") (pintype "input+no_connect"))
    )
    (net (code "95") (name "unconnected-(U4-P5.1{slash}TXD3_2-Pad25)") (class "Default")
      (node (ref "U4") (pin "25") (pinfunction "P5.1/TXD3_2_25") (pintype "input+no_connect"))
    )
    (net (code "96") (name "unconnected-(U4-P5.4{slash}RST{slash}SysClkO{slash}SS_3{slash}CMP--Pad14)") (class "Default")
      (node (ref "U4") (pin "14") (pinfunction "P5.4/RST/SysClkO/SS_3/CMP-_14") (pintype "input+no_connect"))
    )
    (net (code "97") (name "unconnected-(U4-PWM2_2{slash}A15{slash}P2.7-Pad40)") (class "Default")
      (node (ref "U4") (pin "40") (pinfunction "PWM2_2/A15/P2.7_40") (pintype "input+no_connect"))
    )
    (net (code "98") (name "unconnected-(U4-PWM3_2{slash}ALE{slash}P4.5-Pad41)") (class "Default")
      (node (ref "U4") (pin "41") (pinfunction "PWM3_2/ALE/P4.5_41") (pintype "input+no_connect"))
    )
    (net (code "99") (name "unconnected-(U4-PWM6_2{slash}T4{slash}AD7{slash}P0.7-Pad4)") (class "Default")
      (node (ref "U4") (pin "4") (pinfunction "PWM6_2/T4/AD7/P0.7_4") (pintype "input+no_connect"))
    )
    (net (code "100") (name "unconnected-(U4-PWM7_2{slash}T4CLKO{slash}AD6{slash}P0.6-Pad3)") (class "Default")
      (node (ref "U4") (pin "3") (pinfunction "PWM7_2/T4CLKO/AD6/P0.6_3") (pintype "input+no_connect"))
    )
    (net (code "101") (name "unconnected-(U4-PWMFLT_2{slash}T3{slash}AD5{slash}P0.5-Pad2)") (class "Default")
      (node (ref "U4") (pin "2") (pinfunction "PWMFLT_2/T3/AD5/P0.5_2") (pintype "input+no_connect"))
    )
    (net (code "102") (name "unconnected-(U4-PWMFLT{slash}SS_2{slash}ECI_3{slash}A12{slash}P2.4-Pad37)") (class "Default")
      (node (ref "U4") (pin "37") (pinfunction "PWMFLT/SS_2/ECI_3/A12/P2.4_37") (pintype "input+no_connect"))
    )
    (net (code "103") (name "unconnected-(U4-RxD2_2{slash}P4.6-Pad42)") (class "Default")
      (node (ref "U4") (pin "42") (pinfunction "RxD2_2/P4.6_42") (pintype "input+no_connect"))
    )
    (net (code "104") (name "unconnected-(U4-RxD4_2{slash}P5.2-Pad48)") (class "Default")
      (node (ref "U4") (pin "48") (pinfunction "RxD4_2/P5.2_48") (pintype "input+no_connect"))
    )
    (net (code "105") (name "unconnected-(U4-T3CLKO{slash}AD4{slash}P0.4-Pad47)") (class "Default")
      (node (ref "U4") (pin "47") (pinfunction "T3CLKO/AD4/P0.4_47") (pintype "input+no_connect"))
    )
    (net (code "106") (name "unconnected-(U4-TxD2_2{slash}P4.7-Pad7)") (class "Default")
      (node (ref "U4") (pin "7") (pinfunction "TxD2_2/P4.7_7") (pintype "input+no_connect"))
    )
    (net (code "107") (name "unconnected-(U4-TxD4_2{slash}P5.3-Pad1)") (class "Default")
      (node (ref "U4") (pin "1") (pinfunction "TxD4_2/P5.3_1") (pintype "input+no_connect"))
    )
    (net (code "108") (name "unconnected-(U6-VCC1-Pad8)") (class "Default")
      (node (ref "U6") (pin "8") (pinfunction "VCC1_8") (pintype "input+no_connect"))
    )
  )
)
